# obdNode.net
KiCad netlist of a schematic drawn in EAGLE
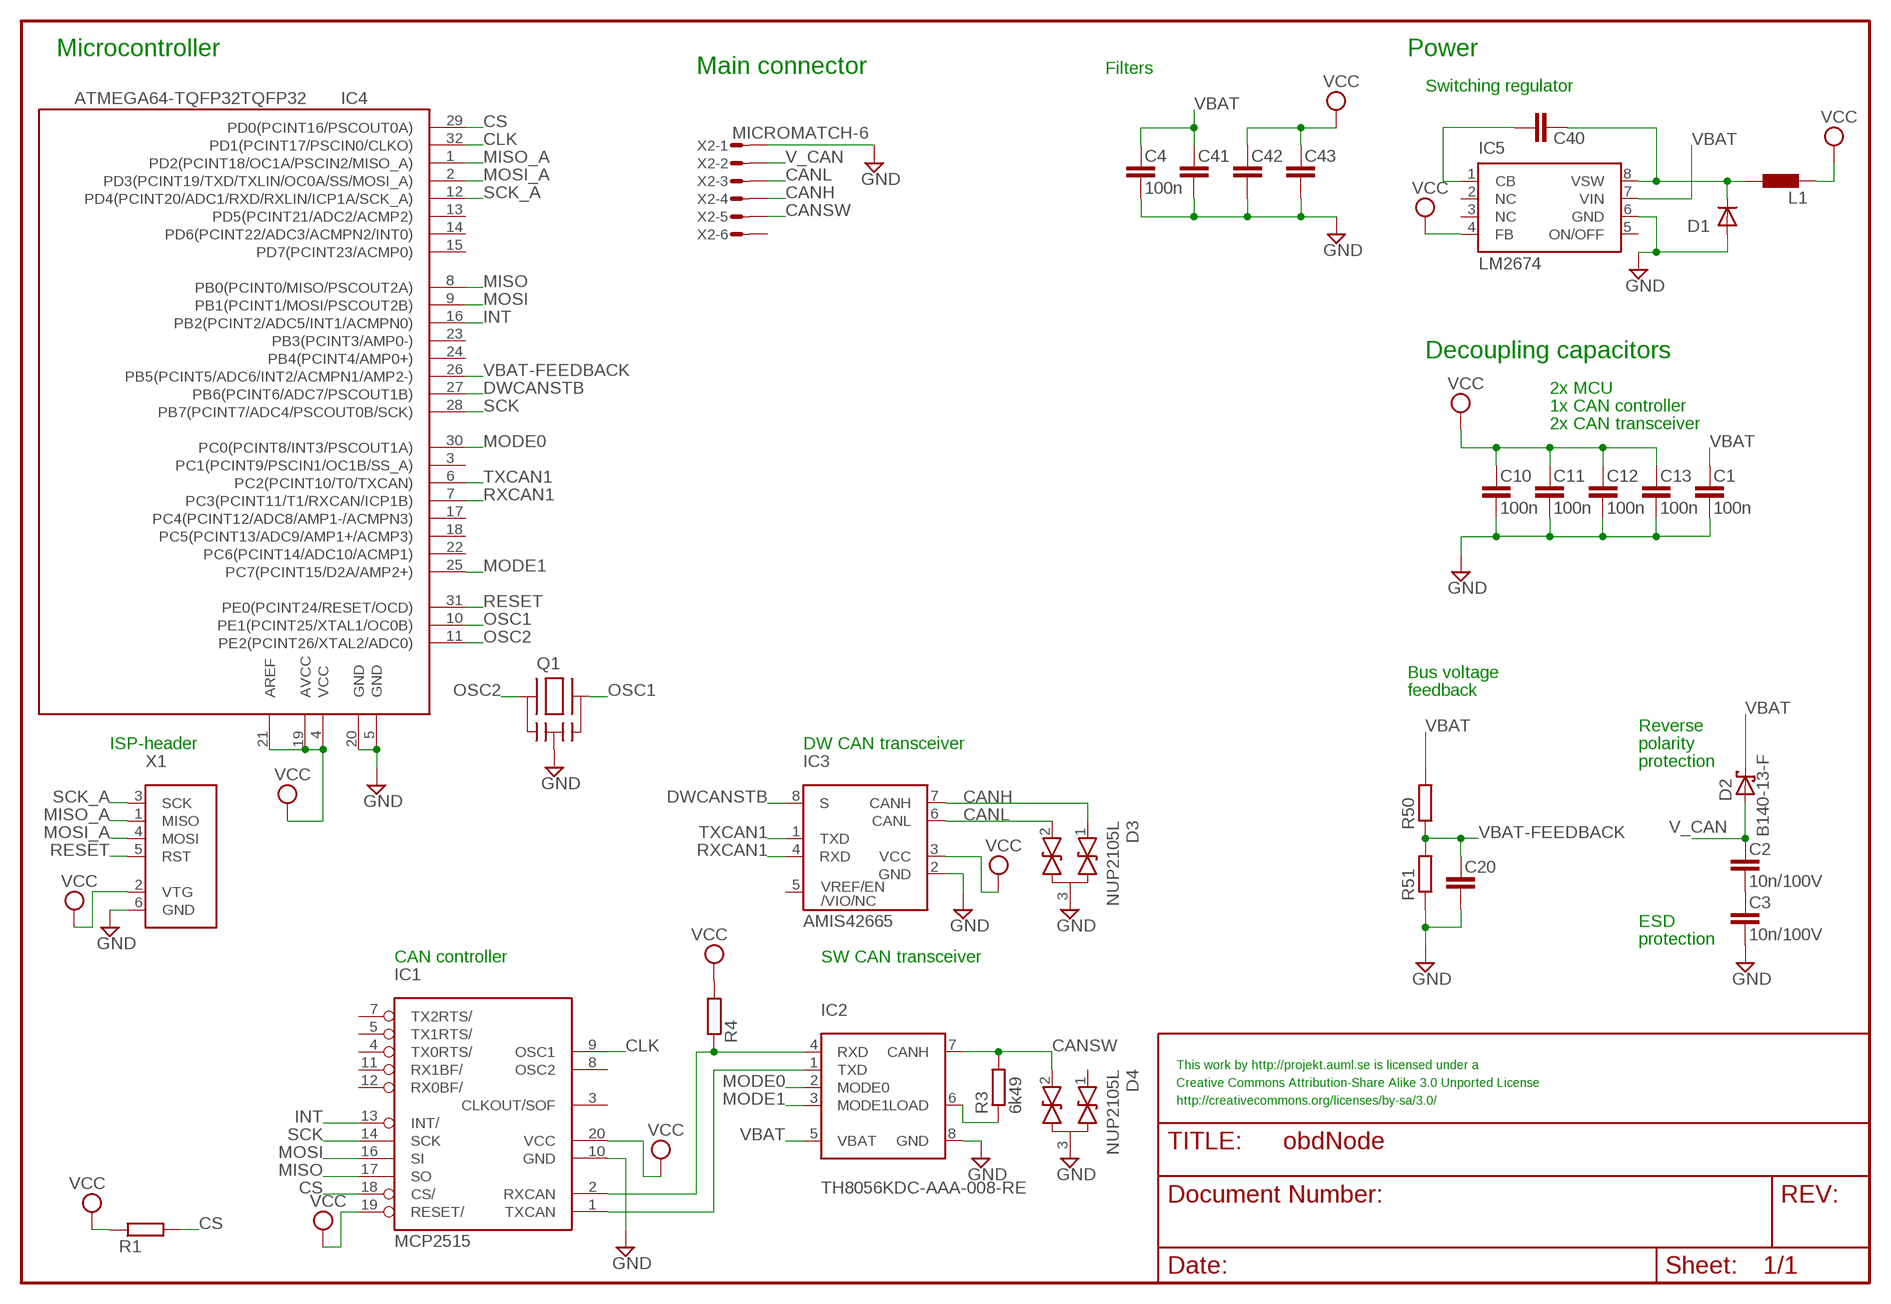
[diagram p0: schematic, sheet 1]

(export (version "E")
  (design (tool "Eeschema 10.0.6"))
  (components
    (comp (ref "C1")
      (value "100n")
      (footprint "eagle-import:C0402")
      (libsource (lib "eagle-import") (part "C-EUC0402"))
    )
    (comp (ref "C2")
      (value "10n/100V")
      (footprint "eagle-import:C0805")
      (libsource (lib "eagle-import") (part "C-EUC0805"))
    )
    (comp (ref "C3")
      (value "10n/100V")
      (footprint "eagle-import:C0805")
      (libsource (lib "eagle-import") (part "C-EUC0805"))
    )
    (comp (ref "C4")
      (value "100n")
      (footprint "eagle-import:C0402")
      (libsource (lib "eagle-import") (part "C-EUC0402"))
    )
    (comp (ref "C10")
      (value "100n")
      (footprint "eagle-import:C0402")
      (libsource (lib "eagle-import") (part "C-EUC0402"))
    )
    (comp (ref "C11")
      (value "100n")
      (footprint "eagle-import:C0402")
      (libsource (lib "eagle-import") (part "C-EUC0402"))
    )
    (comp (ref "C12")
      (value "100n")
      (footprint "eagle-import:C0402")
      (libsource (lib "eagle-import") (part "C-EUC0402"))
    )
    (comp (ref "C13")
      (value "100n")
      (footprint "eagle-import:C0402")
      (libsource (lib "eagle-import") (part "C-EUC0402"))
    )
    (comp (ref "C20")
      (value "C-EUC0402")
      (footprint "eagle-import:C0402")
      (libsource (lib "eagle-import") (part "C-EUC0402"))
    )
    (comp (ref "C40")
      (value "C-EUC0603")
      (footprint "eagle-import:C0603")
      (libsource (lib "eagle-import") (part "C-EUC0603"))
    )
    (comp (ref "C41")
      (value "C-EUC1210")
      (footprint "eagle-import:C1210")
      (libsource (lib "eagle-import") (part "C-EUC1210"))
    )
    (comp (ref "C42")
      (value "C-EUC1210")
      (footprint "eagle-import:C1210")
      (libsource (lib "eagle-import") (part "C-EUC1210"))
    )
    (comp (ref "C43")
      (value "C-EUC0402")
      (footprint "eagle-import:C0402")
      (libsource (lib "eagle-import") (part "C-EUC0402"))
    )
    (comp (ref "D1")
      (value "DIODESMP")
      (footprint "eagle-import:DO-220AA")
      (libsource (lib "eagle-import") (part "DIODESMP"))
    )
    (comp (ref "D2")
      (value "B140-13-F")
      (footprint "eagle-import:SMA")
      (libsource (lib "eagle-import") (part "SCHOTTKY-DIODESMA"))
    )
    (comp (ref "D3")
      (value "NUP2105L")
      (footprint "eagle-import:SOT23")
      (libsource (lib "eagle-import") (part "DUALTVSSOT23"))
    )
    (comp (ref "D4")
      (value "NUP2105L")
      (footprint "eagle-import:SOT23")
      (libsource (lib "eagle-import") (part "DUALTVSSOT23"))
    )
    (comp (ref "IC1")
      (value "MCP2515")
      (footprint "eagle-import:TSSOP")
      (libsource (lib "eagle-import") (part "MCP2515"))
    )
    (comp (ref "IC2")
      (value "TH8056KDC-AAA-008-RE")
      (footprint "eagle-import:SOIC")
      (libsource (lib "eagle-import") (part "TH8056SOIC"))
    )
    (comp (ref "IC3")
      (value "AMIS42665")
      (footprint "eagle-import:SOIC")
      (libsource (lib "eagle-import") (part "AMIS42665"))
    )
    (comp (ref "IC4")
      (value "ATMEGA64-TQFP32TQFP32")
      (footprint "eagle-import:TQFP32")
      (libsource (lib "eagle-import") (part "ATMEGA64-TQFP32TQFP32"))
    )
    (comp (ref "IC5")
      (value "LM2674")
      (footprint "eagle-import:SO8")
      (libsource (lib "eagle-import") (part "LM2674"))
    )
    (comp (ref "L1")
      (value "L-EUL1210")
      (footprint "eagle-import:L1210")
      (libsource (lib "eagle-import") (part "L-EUL1210"))
    )
    (comp (ref "Q1")
      (value "CSTCESMD")
      (footprint "eagle-import:SMD")
      (libsource (lib "eagle-import") (part "CSTCESMD"))
    )
    (comp (ref "R1")
      (value "R-EUR0402")
      (footprint "eagle-import:R0402")
      (libsource (lib "eagle-import") (part "R-EUR0402"))
    )
    (comp (ref "R3")
      (value "6k49")
      (footprint "eagle-import:R0805")
      (libsource (lib "eagle-import") (part "R-EUR0805"))
    )
    (comp (ref "R4")
      (value "R-EUR0402")
      (footprint "eagle-import:R0402")
      (libsource (lib "eagle-import") (part "R-EUR0402"))
    )
    (comp (ref "R50")
      (value "R-EUR0402")
      (footprint "eagle-import:R0402")
      (libsource (lib "eagle-import") (part "R-EUR0402"))
    )
    (comp (ref "R51")
      (value "R-EUR0402")
      (footprint "eagle-import:R0402")
      (libsource (lib "eagle-import") (part "R-EUR0402"))
    )
    (comp (ref "X1")
      (value "AVRISP6PINHEADER")
      (footprint "eagle-import:6PINHEADER")
      (libsource (lib "eagle-import") (part "AVRISP6PINHEADER"))
    )
    (comp (ref "X2")
      (value "MICROMATCH-6")
      (footprint "eagle-import:MICROMATCH-6")
      (libsource (lib "eagle-import") (part "MICROMATCH-6"))
    )
  )
  (nets
    (net (code "1") (name "/CANH") (class "Default")
      (node (ref "D3") (pin "1") (pinfunction "1_1") (pintype "passive"))
      (node (ref "IC3") (pin "7") (pinfunction "CANH_7") (pintype "bidirectional"))
      (node (ref "X2") (pin "4") (pinfunction "S_4") (pintype "passive"))
    )
    (net (code "2") (name "/CANL") (class "Default")
      (node (ref "D3") (pin "2") (pinfunction "2_2") (pintype "passive"))
      (node (ref "IC3") (pin "6") (pinfunction "CANL_6") (pintype "bidirectional"))
      (node (ref "X2") (pin "3") (pinfunction "S_3") (pintype "passive"))
    )
    (net (code "3") (name "/CANSW") (class "Default")
      (node (ref "D4") (pin "2") (pinfunction "2_2") (pintype "passive"))
      (node (ref "IC2") (pin "7") (pinfunction "CANH_7") (pintype "bidirectional"))
      (node (ref "R3") (pin "2") (pinfunction "2_2") (pintype "passive"))
      (node (ref "X2") (pin "5") (pinfunction "S_5") (pintype "passive"))
    )
    (net (code "4") (name "/CLK") (class "Default")
      (node (ref "IC1") (pin "9") (pinfunction "OSC1_9") (pintype "bidirectional"))
      (node (ref "IC4") (pin "32") (pinfunction "PD1(PCINT17/PSCIN0/CLKO)_32") (pintype "bidirectional"))
    )
    (net (code "5") (name "/CS") (class "Default")
      (node (ref "IC1") (pin "18") (pinfunction "CS/_18") (pintype "input"))
      (node (ref "IC4") (pin "29") (pinfunction "PD0(PCINT16/PSCOUT0A)_29") (pintype "bidirectional"))
      (node (ref "R1") (pin "2") (pinfunction "2_2") (pintype "passive"))
    )
    (net (code "6") (name "/DWCANSTB") (class "Default")
      (node (ref "IC3") (pin "8") (pinfunction "S_8") (pintype "bidirectional"))
      (node (ref "IC4") (pin "27") (pinfunction "PB6(PCINT6/ADC7/PSCOUT1B)_27") (pintype "bidirectional"))
    )
    (net (code "7") (name "/INT") (class "Default")
      (node (ref "IC1") (pin "13") (pinfunction "INT/_13") (pintype "output"))
      (node (ref "IC4") (pin "16") (pinfunction "PB2(PCINT2/ADC5/INT1/ACMPN0)_16") (pintype "bidirectional"))
    )
    (net (code "8") (name "/MISO") (class "Default")
      (node (ref "IC1") (pin "17") (pinfunction "SO_17") (pintype "output"))
      (node (ref "IC4") (pin "8") (pinfunction "PB0(PCINT0/MISO/PSCOUT2A)_8") (pintype "bidirectional"))
    )
    (net (code "9") (name "/MISO_A") (class "Default")
      (node (ref "IC4") (pin "1") (pinfunction "PD2(PCINT18/OC1A/PSCIN2/MISO_A)_1") (pintype "bidirectional"))
      (node (ref "X1") (pin "1") (pinfunction "MISO_1") (pintype "bidirectional"))
    )
    (net (code "10") (name "/MODE0") (class "Default")
      (node (ref "IC2") (pin "2") (pinfunction "MODE0_2") (pintype "bidirectional"))
      (node (ref "IC4") (pin "30") (pinfunction "PC0(PCINT8/INT3/PSCOUT1A)_30") (pintype "bidirectional"))
    )
    (net (code "11") (name "/MODE1") (class "Default")
      (node (ref "IC2") (pin "3") (pinfunction "MODE1_3") (pintype "bidirectional"))
      (node (ref "IC4") (pin "25") (pinfunction "PC7(PCINT15/D2A/AMP2+)_25") (pintype "bidirectional"))
    )
    (net (code "12") (name "/MOSI") (class "Default")
      (node (ref "IC1") (pin "16") (pinfunction "SI_16") (pintype "input"))
      (node (ref "IC4") (pin "9") (pinfunction "PB1(PCINT1/MOSI/PSCOUT2B)_9") (pintype "bidirectional"))
    )
    (net (code "13") (name "/MOSI_A") (class "Default")
      (node (ref "IC4") (pin "2") (pinfunction "PD3(PCINT19/TXD/TXLIN/OC0A/SS/MOSI_A)_2") (pintype "bidirectional"))
      (node (ref "X1") (pin "4") (pinfunction "MOSI_4") (pintype "bidirectional"))
    )
    (net (code "14") (name "/OSC1") (class "Default")
      (node (ref "IC4") (pin "10") (pinfunction "PE1(PCINT25/XTAL1/OC0B)_10") (pintype "bidirectional"))
      (node (ref "Q1") (pin "3") (pinfunction "2_3") (pintype "bidirectional"))
    )
    (net (code "15") (name "/OSC2") (class "Default")
      (node (ref "IC4") (pin "11") (pinfunction "PE2(PCINT26/XTAL2/ADC0)_11") (pintype "bidirectional"))
      (node (ref "Q1") (pin "1") (pinfunction "1_1") (pintype "bidirectional"))
    )
    (net (code "16") (name "/RESET") (class "Default")
      (node (ref "IC4") (pin "31") (pinfunction "PE0(PCINT24/RESET/OCD)_31") (pintype "bidirectional"))
      (node (ref "X1") (pin "5") (pinfunction "RST_5") (pintype "bidirectional"))
    )
    (net (code "17") (name "/RXCAN1") (class "Default")
      (node (ref "IC3") (pin "4") (pinfunction "RXD_4") (pintype "bidirectional"))
      (node (ref "IC4") (pin "7") (pinfunction "PC3(PCINT11/T1/RXCAN/ICP1B)_7") (pintype "bidirectional"))
    )
    (net (code "18") (name "/SCK") (class "Default")
      (node (ref "IC1") (pin "14") (pinfunction "SCK_14") (pintype "input"))
      (node (ref "IC4") (pin "28") (pinfunction "PB7(PCINT7/ADC4/PSCOUT0B/SCK)_28") (pintype "bidirectional"))
    )
    (net (code "19") (name "/SCK_A") (class "Default")
      (node (ref "IC4") (pin "12") (pinfunction "PD4(PCINT20/ADC1/RXD/RXLIN/ICP1A/SCK_A)_12") (pintype "bidirectional"))
      (node (ref "X1") (pin "3") (pinfunction "SCK_3") (pintype "bidirectional"))
    )
    (net (code "20") (name "/TXCAN1") (class "Default")
      (node (ref "IC3") (pin "1") (pinfunction "TXD_1") (pintype "bidirectional"))
      (node (ref "IC4") (pin "6") (pinfunction "PC2(PCINT10/T0/TXCAN)_6") (pintype "bidirectional"))
    )
    (net (code "21") (name "/VBAT") (class "Default")
      (node (ref "C1") (pin "1") (pinfunction "1_1") (pintype "passive"))
      (node (ref "C4") (pin "1") (pinfunction "1_1") (pintype "passive"))
      (node (ref "C41") (pin "1") (pinfunction "1_1") (pintype "passive"))
      (node (ref "D2") (pin "C") (pinfunction "C_C") (pintype "passive"))
      (node (ref "IC2") (pin "5") (pinfunction "VBAT_5") (pintype "power_in"))
      (node (ref "IC5") (pin "7") (pinfunction "VIN_7") (pintype "bidirectional"))
      (node (ref "R50") (pin "2") (pinfunction "2_2") (pintype "passive"))
    )
    (net (code "22") (name "/VBAT-FEEDBACK") (class "Default")
      (node (ref "C20") (pin "1") (pinfunction "1_1") (pintype "passive"))
      (node (ref "IC4") (pin "26") (pinfunction "PB5(PCINT5/ADC6/INT2/ACMPN1/AMP2-)_26") (pintype "bidirectional"))
      (node (ref "R50") (pin "1") (pinfunction "1_1") (pintype "passive"))
      (node (ref "R51") (pin "2") (pinfunction "2_2") (pintype "passive"))
    )
    (net (code "23") (name "/V_CAN") (class "Default")
      (node (ref "C2") (pin "1") (pinfunction "1_1") (pintype "passive"))
      (node (ref "D2") (pin "A") (pinfunction "A_A") (pintype "passive"))
      (node (ref "X2") (pin "2") (pinfunction "S_2") (pintype "passive"))
    )
    (net (code "24") (name "GND") (class "Default")
      (node (ref "C1") (pin "2") (pinfunction "2_2") (pintype "passive"))
      (node (ref "C10") (pin "2") (pinfunction "2_2") (pintype "passive"))
      (node (ref "C11") (pin "2") (pinfunction "2_2") (pintype "passive"))
      (node (ref "C12") (pin "2") (pinfunction "2_2") (pintype "passive"))
      (node (ref "C13") (pin "2") (pinfunction "2_2") (pintype "passive"))
      (node (ref "C20") (pin "2") (pinfunction "2_2") (pintype "passive"))
      (node (ref "C3") (pin "2") (pinfunction "2_2") (pintype "passive"))
      (node (ref "C4") (pin "2") (pinfunction "2_2") (pintype "passive"))
      (node (ref "C41") (pin "2") (pinfunction "2_2") (pintype "passive"))
      (node (ref "C42") (pin "2") (pinfunction "2_2") (pintype "passive"))
      (node (ref "C43") (pin "2") (pinfunction "2_2") (pintype "passive"))
      (node (ref "D1") (pin "A") (pinfunction "A_A") (pintype "passive"))
      (node (ref "D3") (pin "3") (pinfunction "3_3") (pintype "passive"))
      (node (ref "D4") (pin "3") (pinfunction "3_3") (pintype "passive"))
      (node (ref "IC1") (pin "10") (pinfunction "GND_10") (pintype "power_in"))
      (node (ref "IC2") (pin "8") (pinfunction "GND_8") (pintype "power_in"))
      (node (ref "IC3") (pin "2") (pinfunction "GND_2") (pintype "power_in"))
      (node (ref "IC4") (pin "20") (pinfunction "GND_20") (pintype "power_in"))
      (node (ref "IC4") (pin "5") (pinfunction "GND_5") (pintype "power_in"))
      (node (ref "IC5") (pin "6") (pinfunction "GND_6") (pintype "bidirectional"))
      (node (ref "Q1") (pin "2") (pinfunction "GND_2") (pintype "bidirectional"))
      (node (ref "R51") (pin "1") (pinfunction "1_1") (pintype "passive"))
      (node (ref "X1") (pin "6") (pinfunction "GND_6") (pintype "bidirectional"))
      (node (ref "X2") (pin "1") (pinfunction "S_1") (pintype "passive"))
    )
    (net (code "25") (name "Net-(C2-Pad2)") (class "Default")
      (node (ref "C2") (pin "2") (pinfunction "2_2") (pintype "passive"))
      (node (ref "C3") (pin "1") (pinfunction "1_1") (pintype "passive"))
    )
    (net (code "26") (name "Net-(IC1-RXCAN)") (class "Default")
      (node (ref "IC1") (pin "2") (pinfunction "RXCAN_2") (pintype "bidirectional"))
      (node (ref "IC2") (pin "4") (pinfunction "RXD_4") (pintype "bidirectional"))
      (node (ref "R4") (pin "1") (pinfunction "1_1") (pintype "passive"))
    )
    (net (code "27") (name "Net-(IC1-TXCAN)") (class "Default")
      (node (ref "IC1") (pin "1") (pinfunction "TXCAN_1") (pintype "bidirectional"))
      (node (ref "IC2") (pin "1") (pinfunction "TXD_1") (pintype "bidirectional"))
    )
    (net (code "28") (name "Net-(IC2-LOAD)") (class "Default")
      (node (ref "IC2") (pin "6") (pinfunction "LOAD_6") (pintype "bidirectional"))
      (node (ref "R3") (pin "1") (pinfunction "1_1") (pintype "passive"))
    )
    (net (code "29") (name "Net-(IC5-CB)") (class "Default")
      (node (ref "C40") (pin "1") (pinfunction "1_1") (pintype "passive"))
      (node (ref "IC5") (pin "1") (pinfunction "CB_1") (pintype "bidirectional"))
    )
    (net (code "30") (name "Net-(IC5-VSW)") (class "Default")
      (node (ref "C40") (pin "2") (pinfunction "2_2") (pintype "passive"))
      (node (ref "D1") (pin "C") (pinfunction "C_C") (pintype "passive"))
      (node (ref "IC5") (pin "8") (pinfunction "VSW_8") (pintype "bidirectional"))
      (node (ref "L1") (pin "2") (pinfunction "P$2_2") (pintype "passive"))
    )
    (net (code "31") (name "VCC") (class "Default")
      (node (ref "C10") (pin "1") (pinfunction "1_1") (pintype "passive"))
      (node (ref "C11") (pin "1") (pinfunction "1_1") (pintype "passive"))
      (node (ref "C12") (pin "1") (pinfunction "1_1") (pintype "passive"))
      (node (ref "C13") (pin "1") (pinfunction "1_1") (pintype "passive"))
      (node (ref "C42") (pin "1") (pinfunction "1_1") (pintype "passive"))
      (node (ref "C43") (pin "1") (pinfunction "1_1") (pintype "passive"))
      (node (ref "IC1") (pin "19") (pinfunction "RESET/_19") (pintype "input"))
      (node (ref "IC1") (pin "20") (pinfunction "VCC_20") (pintype "power_in"))
      (node (ref "IC3") (pin "3") (pinfunction "VCC_3") (pintype "power_in"))
      (node (ref "IC4") (pin "19") (pinfunction "AVCC_19") (pintype "power_in"))
      (node (ref "IC4") (pin "21") (pinfunction "AREF_21") (pintype "passive"))
      (node (ref "IC4") (pin "4") (pinfunction "VCC_4") (pintype "power_in"))
      (node (ref "IC5") (pin "4") (pinfunction "FB_4") (pintype "bidirectional"))
      (node (ref "L1") (pin "1") (pinfunction "P$1_1") (pintype "passive"))
      (node (ref "R1") (pin "1") (pinfunction "1_1") (pintype "passive"))
      (node (ref "R4") (pin "2") (pinfunction "2_2") (pintype "passive"))
      (node (ref "X1") (pin "2") (pinfunction "VTG_2") (pintype "bidirectional"))
    )
    (net (code "32") (name "unconnected-(D4-Pad1)") (class "Default")
      (node (ref "D4") (pin "1") (pinfunction "1_1") (pintype "passive"))
    )
    (net (code "33") (name "unconnected-(IC1-CLKOUT{slash}SOF-Pad3)") (class "Default")
      (node (ref "IC1") (pin "3") (pinfunction "CLKOUT/SOF_3") (pintype "bidirectional"))
    )
    (net (code "34") (name "unconnected-(IC1-OSC2-Pad8)") (class "Default")
      (node (ref "IC1") (pin "8") (pinfunction "OSC2_8") (pintype "bidirectional"))
    )
    (net (code "35") (name "unconnected-(IC1-RX0BF{slash}-Pad12)") (class "Default")
      (node (ref "IC1") (pin "12") (pinfunction "RX0BF/_12") (pintype "bidirectional"))
    )
    (net (code "36") (name "unconnected-(IC1-RX1BF{slash}-Pad11)") (class "Default")
      (node (ref "IC1") (pin "11") (pinfunction "RX1BF/_11") (pintype "bidirectional"))
    )
    (net (code "37") (name "unconnected-(IC1-TX0RTS{slash}-Pad4)") (class "Default")
      (node (ref "IC1") (pin "4") (pinfunction "TX0RTS/_4") (pintype "bidirectional"))
    )
    (net (code "38") (name "unconnected-(IC1-TX1RTS{slash}-Pad5)") (class "Default")
      (node (ref "IC1") (pin "5") (pinfunction "TX1RTS/_5") (pintype "bidirectional"))
    )
    (net (code "39") (name "unconnected-(IC1-TX2RTS{slash}-Pad7)") (class "Default")
      (node (ref "IC1") (pin "7") (pinfunction "TX2RTS/_7") (pintype "bidirectional"))
    )
    (net (code "40") (name "unconnected-(IC3-VREF{slash}EN{slash}VIO{slash}NC-Pad5)") (class "Default")
      (node (ref "IC3") (pin "5") (pinfunction "VREF/EN/VIO/NC_5") (pintype "bidirectional"))
    )
    (net (code "41") (name "unconnected-(IC4-PB3(PCINT3{slash}AMP0-)-Pad23)") (class "Default")
      (node (ref "IC4") (pin "23") (pinfunction "PB3(PCINT3/AMP0-)_23") (pintype "bidirectional"))
    )
    (net (code "42") (name "unconnected-(IC4-PB4(PCINT4{slash}AMP0+)-Pad24)") (class "Default")
      (node (ref "IC4") (pin "24") (pinfunction "PB4(PCINT4/AMP0+)_24") (pintype "bidirectional"))
    )
    (net (code "43") (name "unconnected-(IC4-PC1(PCINT9{slash}PSCIN1{slash}OC1B{slash}SS_A)-Pad3)") (class "Default")
      (node (ref "IC4") (pin "3") (pinfunction "PC1(PCINT9/PSCIN1/OC1B/SS_A)_3") (pintype "bidirectional"))
    )
    (net (code "44") (name "unconnected-(IC4-PC4(PCINT12{slash}ADC8{slash}AMP1-{slash}ACMPN3)-Pad17)") (class "Default")
      (node (ref "IC4") (pin "17") (pinfunction "PC4(PCINT12/ADC8/AMP1-/ACMPN3)_17") (pintype "bidirectional"))
    )
    (net (code "45") (name "unconnected-(IC4-PC5(PCINT13{slash}ADC9{slash}AMP1+{slash}ACMP3)-Pad18)") (class "Default")
      (node (ref "IC4") (pin "18") (pinfunction "PC5(PCINT13/ADC9/AMP1+/ACMP3)_18") (pintype "bidirectional"))
    )
    (net (code "46") (name "unconnected-(IC4-PC6(PCINT14{slash}ADC10{slash}ACMP1)-Pad22)") (class "Default")
      (node (ref "IC4") (pin "22") (pinfunction "PC6(PCINT14/ADC10/ACMP1)_22") (pintype "bidirectional"))
    )
    (net (code "47") (name "unconnected-(IC4-PD5(PCINT21{slash}ADC2{slash}ACMP2)-Pad13)") (class "Default")
      (node (ref "IC4") (pin "13") (pinfunction "PD5(PCINT21/ADC2/ACMP2)_13") (pintype "bidirectional"))
    )
    (net (code "48") (name "unconnected-(IC4-PD6(PCINT22{slash}ADC3{slash}ACMPN2{slash}INT0)-Pad14)") (class "Default")
      (node (ref "IC4") (pin "14") (pinfunction "PD6(PCINT22/ADC3/ACMPN2/INT0)_14") (pintype "bidirectional"))
    )
    (net (code "49") (name "unconnected-(IC4-PD7(PCINT23{slash}ACMP0)-Pad15)") (class "Default")
      (node (ref "IC4") (pin "15") (pinfunction "PD7(PCINT23/ACMP0)_15") (pintype "bidirectional"))
    )
    (net (code "50") (name "unconnected-(IC5-NC-Pad2)") (class "Default")
      (node (ref "IC5") (pin "2") (pinfunction "NC_2") (pintype "no_connect"))
    )
    (net (code "51") (name "unconnected-(IC5-NC-Pad3)") (class "Default")
      (node (ref "IC5") (pin "3") (pinfunction "NC_3") (pintype "no_connect"))
    )
    (net (code "52") (name "unconnected-(IC5-ON{slash}OFF-Pad5)") (class "Default")
      (node (ref "IC5") (pin "5") (pinfunction "ON/OFF_5") (pintype "bidirectional"))
    )
    (net (code "53") (name "unconnected-(X2F-S-Pad6)") (class "Default")
      (node (ref "X2") (pin "6") (pinfunction "S_6") (pintype "passive"))
    )
  )
)
